# Acoustics_4.net
KiCad netlist of a schematic drawn in Altium Designer
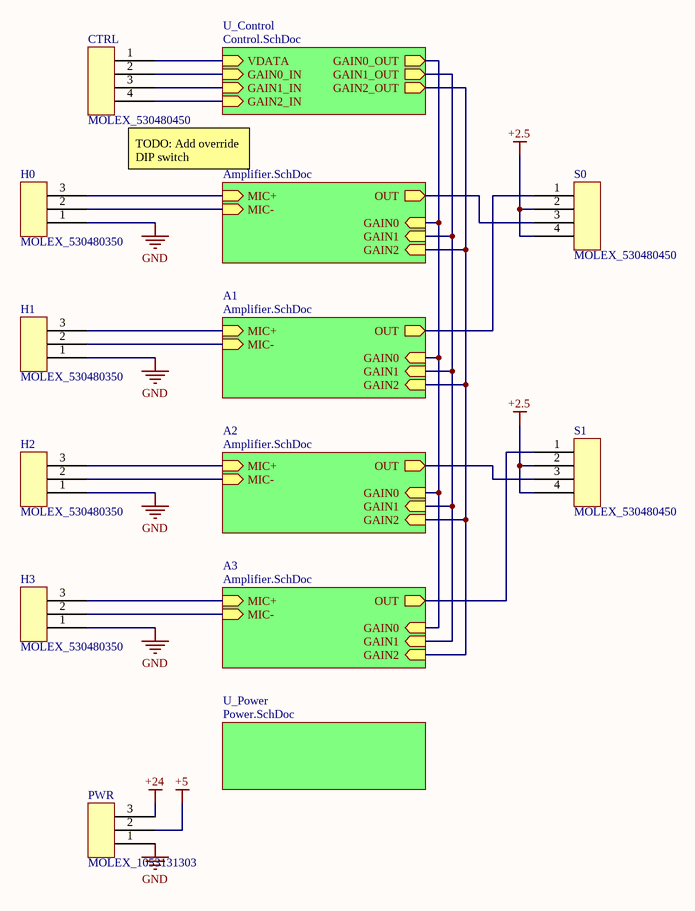
[diagram p0: Acoustics_4.SchDoc]

(export (version "E")
  (design (tool "Eeschema 10.0.6"))
  (components
    (comp (ref "CTRL")
      (value "MOLEX_530480450")
      (footprint "MOLEX_530480450")
      (libsource (lib "") (part "MOLEX_530480450_1"))
    )
    (comp (ref "H0")
      (value "MOLEX_530480350")
      (footprint "MOLEX_530480350")
      (libsource (lib "Acoustics") (part "MOLEX_530480350"))
    )
    (comp (ref "H1")
      (value "MOLEX_530480350")
      (footprint "MOLEX_530480350")
      (libsource (lib "Acoustics") (part "MOLEX_530480350"))
    )
    (comp (ref "H2")
      (value "MOLEX_530480350")
      (footprint "MOLEX_530480350")
      (libsource (lib "Acoustics") (part "MOLEX_530480350"))
    )
    (comp (ref "H3")
      (value "MOLEX_530480350")
      (footprint "MOLEX_530480350")
      (libsource (lib "Acoustics") (part "MOLEX_530480350"))
    )
    (comp (ref "PWR")
      (value "MOLEX_1053131303")
      (footprint "MOLEX_1053131303")
      (libsource (lib "Acoustics") (part "MOLEX_1053131303"))
    )
    (comp (ref "S0")
      (value "MOLEX_530480450")
      (footprint "MOLEX_530480450")
      (libsource (lib "Acoustics") (part "MOLEX_530480450"))
    )
    (comp (ref "S1")
      (value "MOLEX_530480450")
      (footprint "MOLEX_530480450")
      (libsource (lib "Acoustics") (part "MOLEX_530480450"))
    )
  )
  (nets
    (net (code "1") (name "+2.5") (class "Default")
      (node (ref "S0") (pin "2") (pintype "passive"))
      (node (ref "S0") (pin "4") (pintype "passive"))
      (node (ref "S1") (pin "2") (pintype "passive"))
      (node (ref "S1") (pin "4") (pintype "passive"))
    )
    (net (code "2") (name "+5") (class "Default") (node (ref "PWR") (pin "2") (pintype "power_in")))
    (net (code "3") (name "+24") (class "Default") (node (ref "PWR") (pin "3") (pintype "power_in")))
    (net (code "4") (name "/GAIN0_IN") (class "Default") (node (ref "CTRL") (pin "2") (pintype "passive")))
    (net (code "6") (name "/GAIN1_IN") (class "Default") (node (ref "CTRL") (pin "3") (pintype "passive")))
    (net (code "8") (name "/GAIN2_IN") (class "Default") (node (ref "CTRL") (pin "4") (pintype "passive")))
    (net (code "10") (name "/MIC+") (class "Default") (node (ref "H0") (pin "3") (pintype "passive")))
    (net (code "11") (name "/MIC+_1") (class "Default") (node (ref "H2") (pin "3") (pintype "passive")))
    (net (code "12") (name "/MIC+_2") (class "Default") (node (ref "H1") (pin "3") (pintype "passive")))
    (net (code "13") (name "/MIC+_3") (class "Default") (node (ref "H3") (pin "3") (pintype "passive")))
    (net (code "14") (name "/MIC-") (class "Default") (node (ref "H0") (pin "2") (pintype "passive")))
    (net (code "15") (name "/MIC-_1") (class "Default") (node (ref "H2") (pin "2") (pintype "passive")))
    (net (code "16") (name "/MIC-_2") (class "Default") (node (ref "H1") (pin "2") (pintype "passive")))
    (net (code "17") (name "/MIC-_3") (class "Default") (node (ref "H3") (pin "2") (pintype "passive")))
    (net (code "18") (name "/OUT") (class "Default") (node (ref "S0") (pin "3") (pintype "passive")))
    (net (code "19") (name "/OUT_1") (class "Default") (node (ref "S1") (pin "3") (pintype "passive")))
    (net (code "20") (name "/OUT_2") (class "Default") (node (ref "S1") (pin "1") (pintype "passive")))
    (net (code "21") (name "/OUT_3") (class "Default") (node (ref "S0") (pin "1") (pintype "passive")))
    (net (code "22") (name "/VDATA") (class "Default") (node (ref "CTRL") (pin "1") (pintype "passive")))
    (net (code "23") (name "GND") (class "Default")
      (node (ref "H0") (pin "1") (pintype "passive"))
      (node (ref "H1") (pin "1") (pintype "passive"))
      (node (ref "H2") (pin "1") (pintype "passive"))
      (node (ref "H3") (pin "1") (pintype "passive"))
      (node (ref "PWR") (pin "1") (pintype "power_in"))
    )
  )
)
